# PIC_PROTO-BOARD.net
KiCad netlist of a schematic drawn in EAGLE
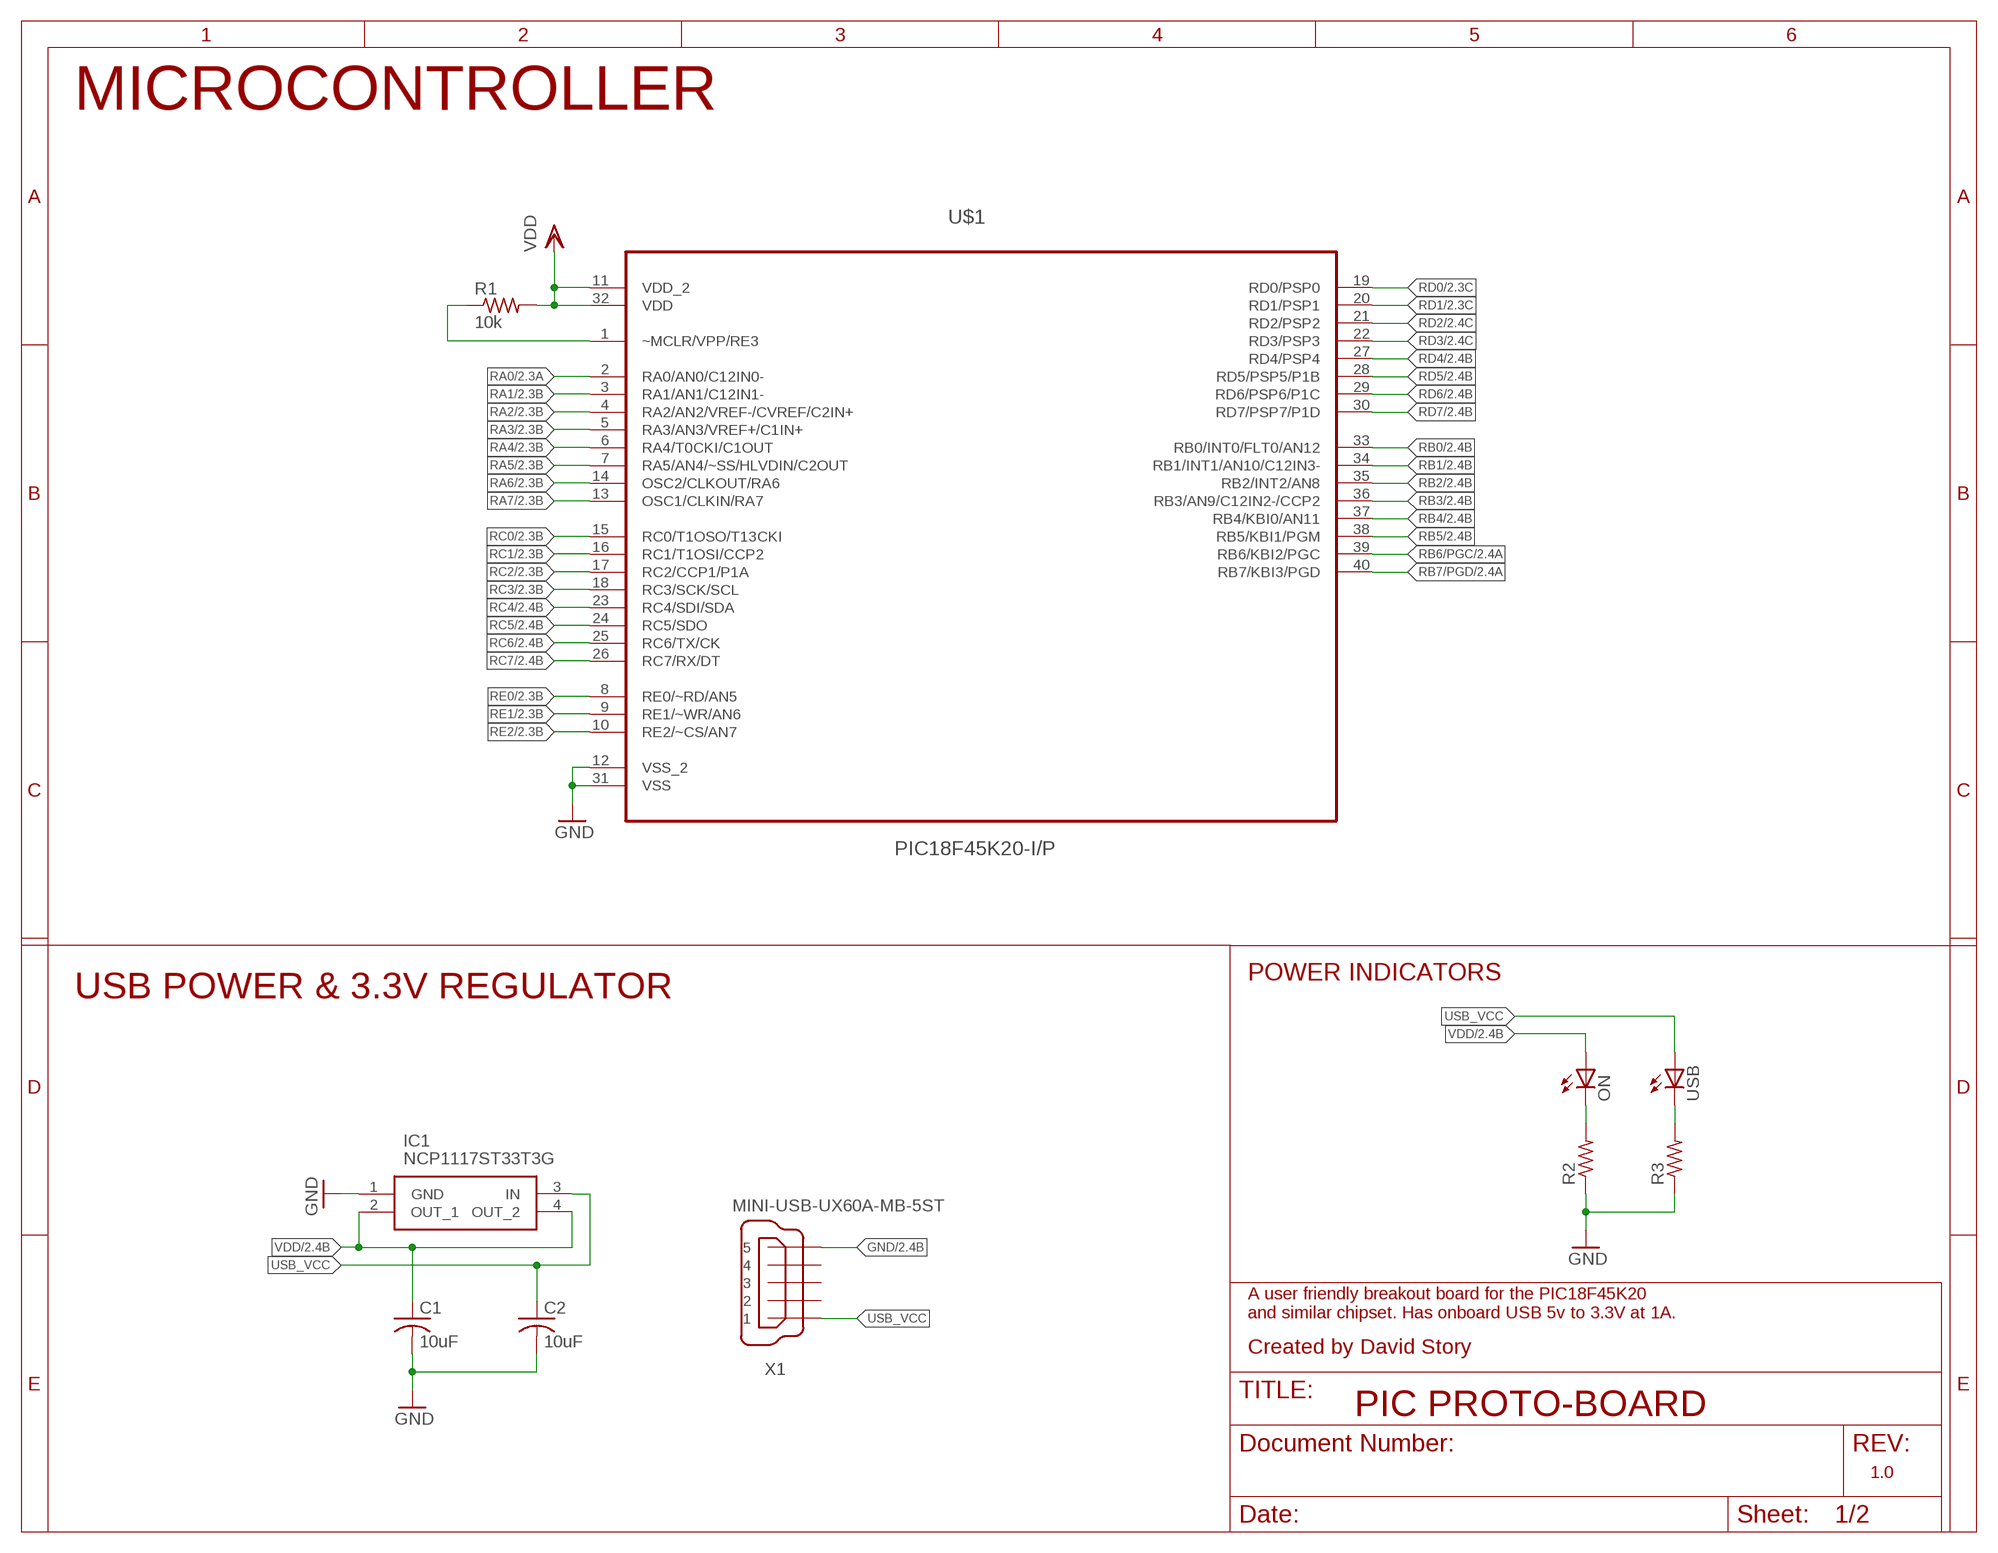
[diagram p0: schematic, sheet 1]
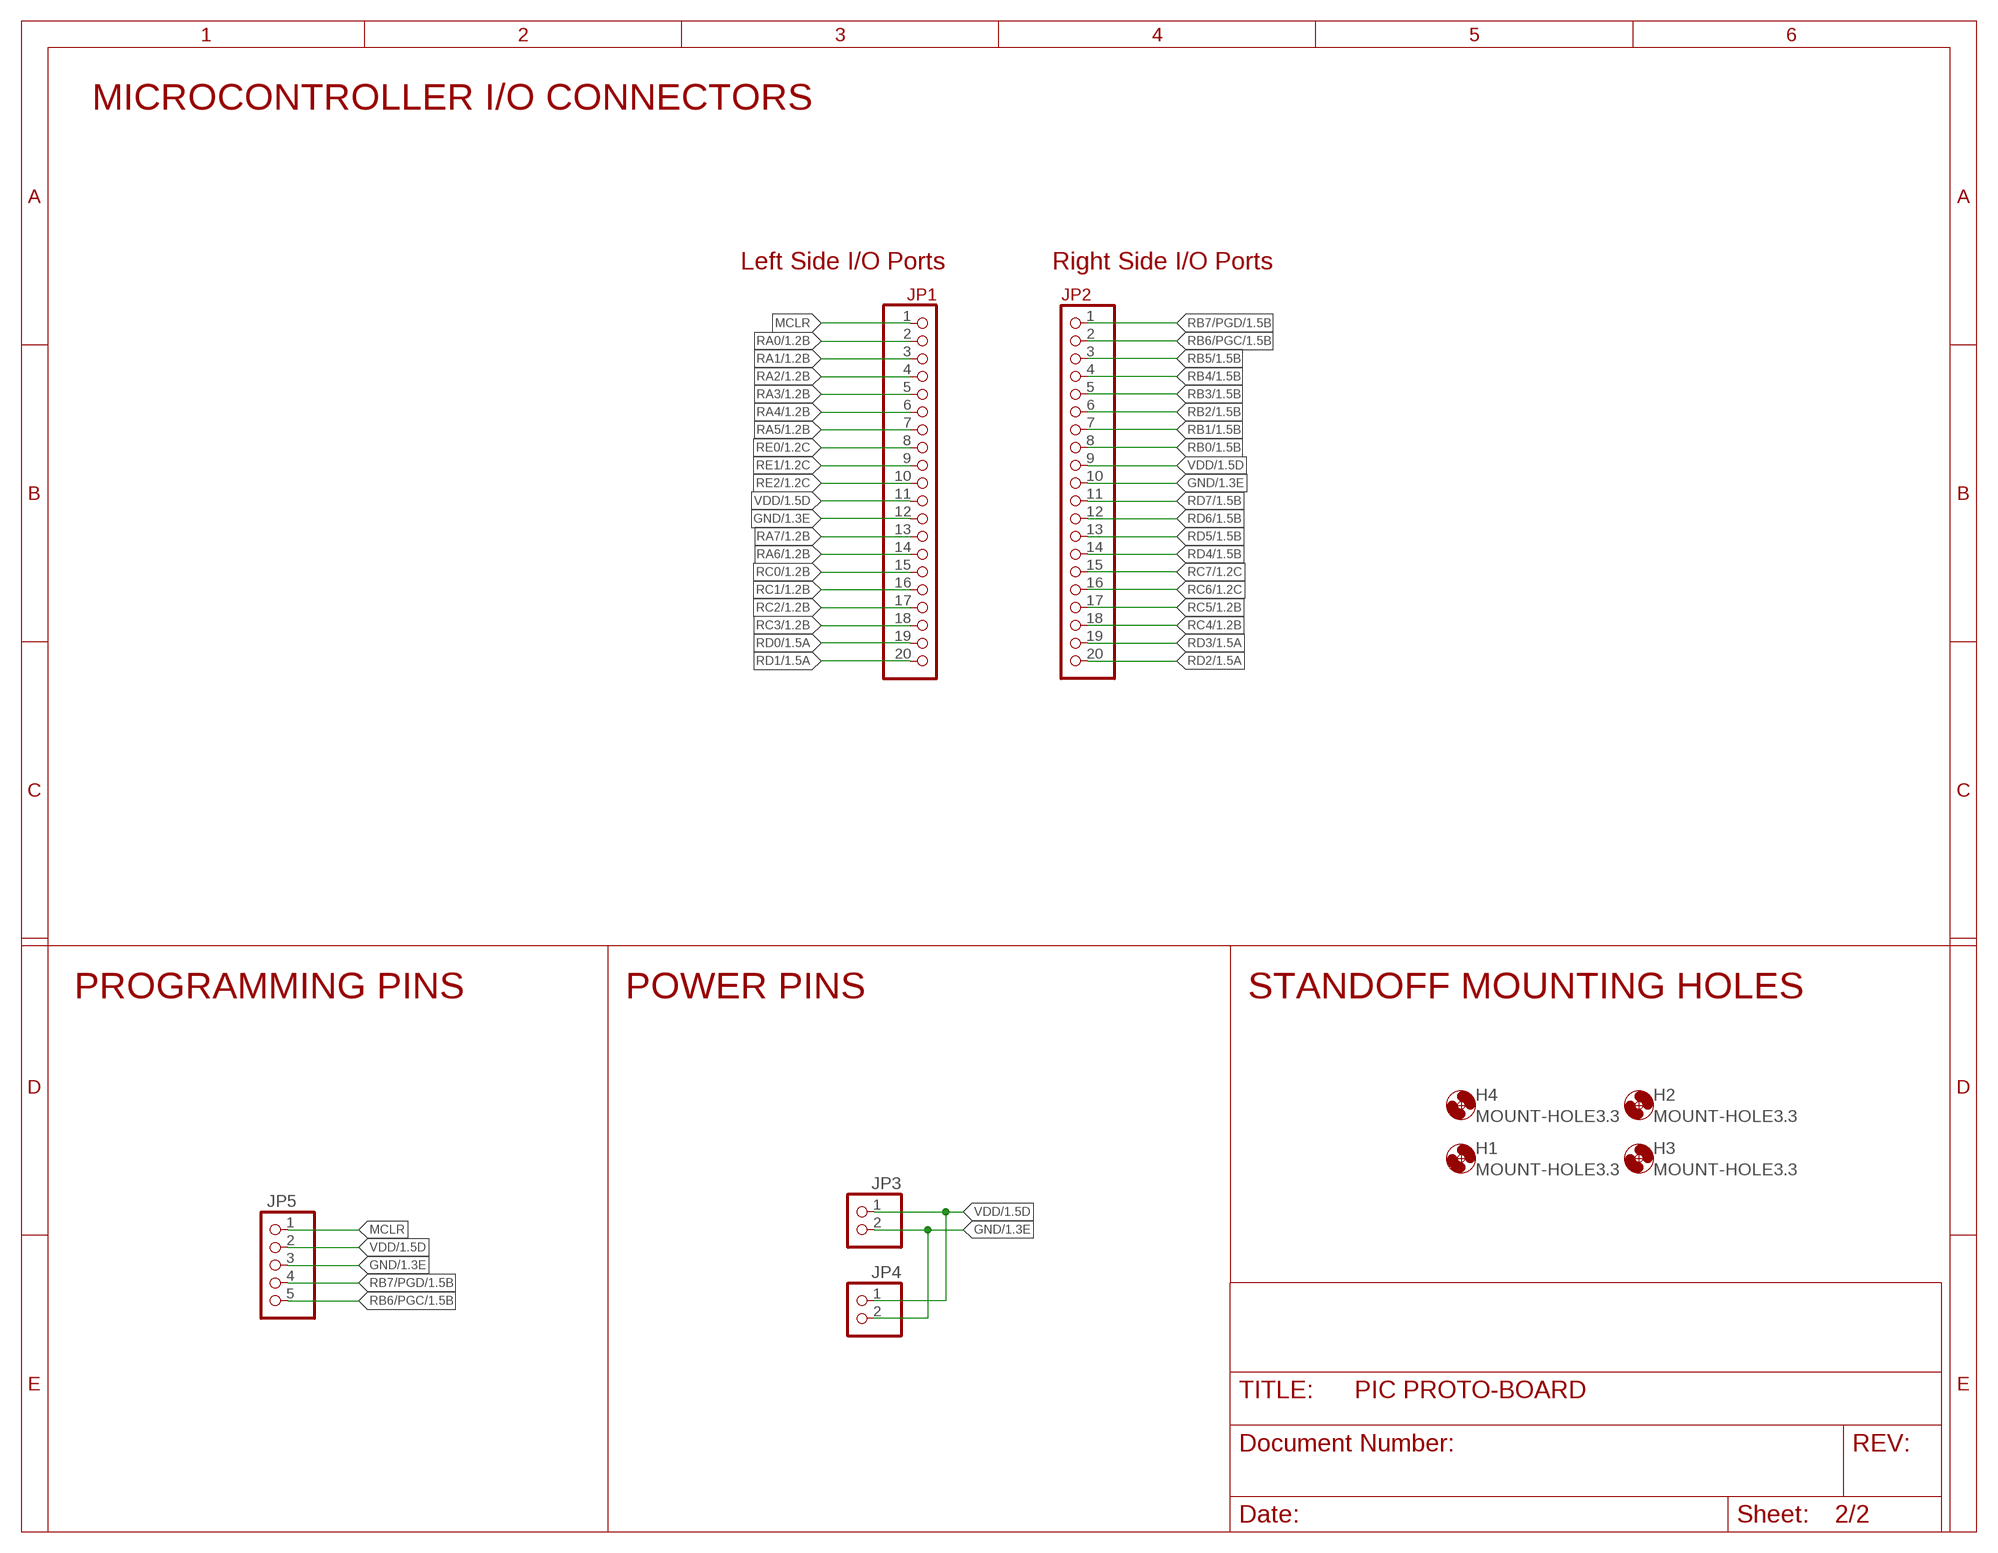
[diagram p1: schematic, sheet 2]

(export (version "E")
  (design (tool "Eeschema 10.0.6"))
  (components
    (comp (ref "C1")
      (value "10uF")
      (footprint "eagle-import:C0805")
      (libsource (lib "eagle-import") (part "C-USC0805"))
    )
    (comp (ref "C2")
      (value "10uF")
      (footprint "eagle-import:C0805")
      (libsource (lib "eagle-import") (part "C-USC0805"))
    )
    (comp (ref "IC1")
      (value "NCP1117ST33T3G")
      (footprint "eagle-import:SOT230P700X180-4N")
      (fields (field (name "MOUSER_PART_NUMBER") "863-NCP1117ST33T3G"))
      (libsource (lib "eagle-import") (part "NCP1117ST33T3G"))
    )
    (comp (ref "ON")
      (value "LEDCHIP-LED0603")
      (footprint "eagle-import:CHIP-LED0603")
      (libsource (lib "eagle-import") (part "LEDCHIP-LED0603"))
    )
    (comp (ref "R1")
      (value "10k")
      (footprint "eagle-import:R0805")
      (libsource (lib "eagle-import") (part "R-US_R0805"))
    )
    (comp (ref "R2")
      (value "R-US_R0603")
      (footprint "eagle-import:R0603")
      (libsource (lib "eagle-import") (part "R-US_R0603"))
    )
    (comp (ref "R3")
      (value "R-US_R0603")
      (footprint "eagle-import:R0603")
      (libsource (lib "eagle-import") (part "R-US_R0603"))
    )
    (comp (ref "U$1")
      (value "PIC18F45K20-I/P")
      (footprint "eagle-import:DIP254P1524X635-40")
      (libsource (lib "eagle-import") (part "PIC18F45K20-I/P"))
    )
    (comp (ref "USB")
      (value "LEDCHIP-LED0603")
      (footprint "eagle-import:CHIP-LED0603")
      (libsource (lib "eagle-import") (part "LEDCHIP-LED0603"))
    )
    (comp (ref "X1")
      (value "MINI-USB-UX60A-MB-5ST")
      (footprint "eagle-import:UX60A-MB-5ST")
      (libsource (lib "eagle-import") (part "MINI-USB-UX60A-MB-5ST"))
    )
    (comp (ref "H1")
      (value "MOUNT-HOLE3.3")
      (footprint "eagle-import:3,3")
      (libsource (lib "eagle-import") (part "MOUNT-HOLE3.3"))
    )
    (comp (ref "H2")
      (value "MOUNT-HOLE3.3")
      (footprint "eagle-import:3,3")
      (libsource (lib "eagle-import") (part "MOUNT-HOLE3.3"))
    )
    (comp (ref "H3")
      (value "MOUNT-HOLE3.3")
      (footprint "eagle-import:3,3")
      (libsource (lib "eagle-import") (part "MOUNT-HOLE3.3"))
    )
    (comp (ref "H4")
      (value "MOUNT-HOLE3.3")
      (footprint "eagle-import:3,3")
      (libsource (lib "eagle-import") (part "MOUNT-HOLE3.3"))
    )
    (comp (ref "JP1")
      (value "PINHD-1X20")
      (footprint "eagle-import:1X20")
      (libsource (lib "eagle-import") (part "PINHD-1X20"))
    )
    (comp (ref "JP2")
      (value "PINHD-1X20")
      (footprint "eagle-import:1X20")
      (libsource (lib "eagle-import") (part "PINHD-1X20"))
    )
    (comp (ref "JP3")
      (value "PINHD-1X2")
      (footprint "eagle-import:1X02")
      (libsource (lib "eagle-import") (part "PINHD-1X2"))
    )
    (comp (ref "JP4")
      (value "PINHD-1X2")
      (footprint "eagle-import:1X02")
      (libsource (lib "eagle-import") (part "PINHD-1X2"))
    )
    (comp (ref "JP5")
      (value "PINHD-1X5")
      (footprint "eagle-import:1X05")
      (libsource (lib "eagle-import") (part "PINHD-1X5"))
    )
  )
  (nets
    (net (code "1") (name "GND") (class "Default")
      (node (ref "C1") (pin "2") (pinfunction "2_2") (pintype "passive"))
      (node (ref "C2") (pin "2") (pinfunction "2_2") (pintype "passive"))
      (node (ref "IC1") (pin "1") (pinfunction "GND_1") (pintype "power_in"))
      (node (ref "JP1") (pin "12") (pinfunction "12_12") (pintype "passive"))
      (node (ref "JP2") (pin "10") (pinfunction "10_10") (pintype "passive"))
      (node (ref "JP3") (pin "2") (pinfunction "2_2") (pintype "passive"))
      (node (ref "JP4") (pin "2") (pinfunction "2_2") (pintype "passive"))
      (node (ref "JP5") (pin "3") (pinfunction "3_3") (pintype "passive"))
      (node (ref "R2") (pin "1") (pinfunction "1_1") (pintype "passive"))
      (node (ref "R3") (pin "1") (pinfunction "1_1") (pintype "passive"))
      (node (ref "U$1") (pin "12") (pinfunction "VSS_2_12") (pintype "power_in"))
      (node (ref "U$1") (pin "31") (pinfunction "VSS_31") (pintype "power_in"))
      (node (ref "X1") (pin "5") (pinfunction "5_5") (pintype "input"))
    )
    (net (code "2") (name "MCLR") (class "Default")
      (node (ref "JP1") (pin "1") (pinfunction "1_1") (pintype "passive"))
      (node (ref "JP5") (pin "1") (pinfunction "1_1") (pintype "passive"))
      (node (ref "R1") (pin "1") (pinfunction "1_1") (pintype "passive"))
      (node (ref "U$1") (pin "1") (pinfunction "~{MCLR/VPP/RE3}_1") (pintype "input"))
    )
    (net (code "3") (name "Net-(ON-PadC)") (class "Default")
      (node (ref "ON") (pin "C") (pinfunction "C_C") (pintype "passive"))
      (node (ref "R2") (pin "2") (pinfunction "2_2") (pintype "passive"))
    )
    (net (code "4") (name "Net-(R3-Pad2)") (class "Default")
      (node (ref "R3") (pin "2") (pinfunction "2_2") (pintype "passive"))
      (node (ref "USB") (pin "C") (pinfunction "C_C") (pintype "passive"))
    )
    (net (code "5") (name "RA0") (class "Default")
      (node (ref "JP1") (pin "2") (pinfunction "2_2") (pintype "passive"))
      (node (ref "U$1") (pin "2") (pinfunction "RA0/AN0/C12IN0-_2") (pintype "bidirectional"))
    )
    (net (code "6") (name "RA1") (class "Default")
      (node (ref "JP1") (pin "3") (pinfunction "3_3") (pintype "passive"))
      (node (ref "U$1") (pin "3") (pinfunction "RA1/AN1/C12IN1-_3") (pintype "bidirectional"))
    )
    (net (code "7") (name "RA2") (class "Default")
      (node (ref "JP1") (pin "4") (pinfunction "4_4") (pintype "passive"))
      (node (ref "U$1") (pin "4") (pinfunction "RA2/AN2/VREF-/CVREF/C2IN+_4") (pintype "bidirectional"))
    )
    (net (code "8") (name "RA3") (class "Default")
      (node (ref "JP1") (pin "5") (pinfunction "5_5") (pintype "passive"))
      (node (ref "U$1") (pin "5") (pinfunction "RA3/AN3/VREF+/C1IN+_5") (pintype "bidirectional"))
    )
    (net (code "9") (name "RA4") (class "Default")
      (node (ref "JP1") (pin "6") (pinfunction "6_6") (pintype "passive"))
      (node (ref "U$1") (pin "6") (pinfunction "RA4/T0CKI/C1OUT_6") (pintype "bidirectional"))
    )
    (net (code "10") (name "RA5") (class "Default")
      (node (ref "JP1") (pin "7") (pinfunction "7_7") (pintype "passive"))
      (node (ref "U$1") (pin "7") (pinfunction "RA5/AN4/~{SS/HLVDIN/C2OUT}_7") (pintype "bidirectional"))
    )
    (net (code "11") (name "RA6") (class "Default")
      (node (ref "JP1") (pin "14") (pinfunction "14_14") (pintype "passive"))
      (node (ref "U$1") (pin "14") (pinfunction "OSC2/CLKOUT/RA6_14") (pintype "bidirectional"))
    )
    (net (code "12") (name "RA7") (class "Default")
      (node (ref "JP1") (pin "13") (pinfunction "13_13") (pintype "passive"))
      (node (ref "U$1") (pin "13") (pinfunction "OSC1/CLKIN/RA7_13") (pintype "bidirectional"))
    )
    (net (code "13") (name "RB0") (class "Default")
      (node (ref "JP2") (pin "8") (pinfunction "8_8") (pintype "passive"))
      (node (ref "U$1") (pin "33") (pinfunction "RB0/INT0/FLT0/AN12_33") (pintype "bidirectional"))
    )
    (net (code "14") (name "RB1") (class "Default")
      (node (ref "JP2") (pin "7") (pinfunction "7_7") (pintype "passive"))
      (node (ref "U$1") (pin "34") (pinfunction "RB1/INT1/AN10/C12IN3-_34") (pintype "bidirectional"))
    )
    (net (code "15") (name "RB2") (class "Default")
      (node (ref "JP2") (pin "6") (pinfunction "6_6") (pintype "passive"))
      (node (ref "U$1") (pin "35") (pinfunction "RB2/INT2/AN8_35") (pintype "bidirectional"))
    )
    (net (code "16") (name "RB3") (class "Default")
      (node (ref "JP2") (pin "5") (pinfunction "5_5") (pintype "passive"))
      (node (ref "U$1") (pin "36") (pinfunction "RB3/AN9/C12IN2-/CCP2_36") (pintype "bidirectional"))
    )
    (net (code "17") (name "RB4") (class "Default")
      (node (ref "JP2") (pin "4") (pinfunction "4_4") (pintype "passive"))
      (node (ref "U$1") (pin "37") (pinfunction "RB4/KBI0/AN11_37") (pintype "bidirectional"))
    )
    (net (code "18") (name "RB5") (class "Default")
      (node (ref "JP2") (pin "3") (pinfunction "3_3") (pintype "passive"))
      (node (ref "U$1") (pin "38") (pinfunction "RB5/KBI1/PGM_38") (pintype "bidirectional"))
    )
    (net (code "19") (name "RB6{slash}PGC") (class "Default")
      (node (ref "JP2") (pin "2") (pinfunction "2_2") (pintype "passive"))
      (node (ref "JP5") (pin "5") (pinfunction "5_5") (pintype "passive"))
      (node (ref "U$1") (pin "39") (pinfunction "RB6/KBI2/PGC_39") (pintype "bidirectional"))
    )
    (net (code "20") (name "RB7{slash}PGD") (class "Default")
      (node (ref "JP2") (pin "1") (pinfunction "1_1") (pintype "passive"))
      (node (ref "JP5") (pin "4") (pinfunction "4_4") (pintype "passive"))
      (node (ref "U$1") (pin "40") (pinfunction "RB7/KBI3/PGD_40") (pintype "bidirectional"))
    )
    (net (code "21") (name "RC0") (class "Default")
      (node (ref "JP1") (pin "15") (pinfunction "15_15") (pintype "passive"))
      (node (ref "U$1") (pin "15") (pinfunction "RC0/T1OSO/T13CKI_15") (pintype "bidirectional"))
    )
    (net (code "22") (name "RC1") (class "Default")
      (node (ref "JP1") (pin "16") (pinfunction "16_16") (pintype "passive"))
      (node (ref "U$1") (pin "16") (pinfunction "RC1/T1OSI/CCP2_16") (pintype "bidirectional"))
    )
    (net (code "23") (name "RC2") (class "Default")
      (node (ref "JP1") (pin "17") (pinfunction "17_17") (pintype "passive"))
      (node (ref "U$1") (pin "17") (pinfunction "RC2/CCP1/P1A_17") (pintype "bidirectional"))
    )
    (net (code "24") (name "RC3") (class "Default")
      (node (ref "JP1") (pin "18") (pinfunction "18_18") (pintype "passive"))
      (node (ref "U$1") (pin "18") (pinfunction "RC3/SCK/SCL_18") (pintype "bidirectional"))
    )
    (net (code "25") (name "RC4") (class "Default")
      (node (ref "JP2") (pin "18") (pinfunction "18_18") (pintype "passive"))
      (node (ref "U$1") (pin "23") (pinfunction "RC4/SDI/SDA_23") (pintype "bidirectional"))
    )
    (net (code "26") (name "RC5") (class "Default")
      (node (ref "JP2") (pin "17") (pinfunction "17_17") (pintype "passive"))
      (node (ref "U$1") (pin "24") (pinfunction "RC5/SDO_24") (pintype "bidirectional"))
    )
    (net (code "27") (name "RC6") (class "Default")
      (node (ref "JP2") (pin "16") (pinfunction "16_16") (pintype "passive"))
      (node (ref "U$1") (pin "25") (pinfunction "RC6/TX/CK_25") (pintype "bidirectional"))
    )
    (net (code "28") (name "RC7") (class "Default")
      (node (ref "JP2") (pin "15") (pinfunction "15_15") (pintype "passive"))
      (node (ref "U$1") (pin "26") (pinfunction "RC7/RX/DT_26") (pintype "bidirectional"))
    )
    (net (code "29") (name "RD0") (class "Default")
      (node (ref "JP1") (pin "19") (pinfunction "19_19") (pintype "passive"))
      (node (ref "U$1") (pin "19") (pinfunction "RD0/PSP0_19") (pintype "bidirectional"))
    )
    (net (code "30") (name "RD1") (class "Default")
      (node (ref "JP1") (pin "20") (pinfunction "20_20") (pintype "passive"))
      (node (ref "U$1") (pin "20") (pinfunction "RD1/PSP1_20") (pintype "bidirectional"))
    )
    (net (code "31") (name "RD2") (class "Default")
      (node (ref "JP2") (pin "20") (pinfunction "20_20") (pintype "passive"))
      (node (ref "U$1") (pin "21") (pinfunction "RD2/PSP2_21") (pintype "bidirectional"))
    )
    (net (code "32") (name "RD3") (class "Default")
      (node (ref "JP2") (pin "19") (pinfunction "19_19") (pintype "passive"))
      (node (ref "U$1") (pin "22") (pinfunction "RD3/PSP3_22") (pintype "bidirectional"))
    )
    (net (code "33") (name "RD4") (class "Default")
      (node (ref "JP2") (pin "14") (pinfunction "14_14") (pintype "passive"))
      (node (ref "U$1") (pin "27") (pinfunction "RD4/PSP4_27") (pintype "bidirectional"))
    )
    (net (code "34") (name "RD5") (class "Default")
      (node (ref "JP2") (pin "13") (pinfunction "13_13") (pintype "passive"))
      (node (ref "U$1") (pin "28") (pinfunction "RD5/PSP5/P1B_28") (pintype "bidirectional"))
    )
    (net (code "35") (name "RD6") (class "Default")
      (node (ref "JP2") (pin "12") (pinfunction "12_12") (pintype "passive"))
      (node (ref "U$1") (pin "29") (pinfunction "RD6/PSP6/P1C_29") (pintype "bidirectional"))
    )
    (net (code "36") (name "RD7") (class "Default")
      (node (ref "JP2") (pin "11") (pinfunction "11_11") (pintype "passive"))
      (node (ref "U$1") (pin "30") (pinfunction "RD7/PSP7/P1D_30") (pintype "bidirectional"))
    )
    (net (code "37") (name "RE0") (class "Default")
      (node (ref "JP1") (pin "8") (pinfunction "8_8") (pintype "passive"))
      (node (ref "U$1") (pin "8") (pinfunction "RE0/~{RD/AN5}_8") (pintype "bidirectional"))
    )
    (net (code "38") (name "RE1") (class "Default")
      (node (ref "JP1") (pin "9") (pinfunction "9_9") (pintype "passive"))
      (node (ref "U$1") (pin "9") (pinfunction "RE1/~{WR/AN6}_9") (pintype "bidirectional"))
    )
    (net (code "39") (name "RE2") (class "Default")
      (node (ref "JP1") (pin "10") (pinfunction "10_10") (pintype "passive"))
      (node (ref "U$1") (pin "10") (pinfunction "RE2/~{CS/AN7}_10") (pintype "bidirectional"))
    )
    (net (code "40") (name "USB_VCC") (class "Default")
      (node (ref "C2") (pin "1") (pinfunction "1_1") (pintype "passive"))
      (node (ref "IC1") (pin "3") (pinfunction "IN_3") (pintype "input"))
      (node (ref "USB") (pin "A") (pinfunction "A_A") (pintype "passive"))
      (node (ref "X1") (pin "1") (pinfunction "1_1") (pintype "input"))
    )
    (net (code "41") (name "VDD") (class "Default")
      (node (ref "C1") (pin "1") (pinfunction "1_1") (pintype "passive"))
      (node (ref "IC1") (pin "2") (pinfunction "OUT_1_2") (pintype "output"))
      (node (ref "IC1") (pin "4") (pinfunction "OUT_2_4") (pintype "output"))
      (node (ref "JP1") (pin "11") (pinfunction "11_11") (pintype "passive"))
      (node (ref "JP2") (pin "9") (pinfunction "9_9") (pintype "passive"))
      (node (ref "JP3") (pin "1") (pinfunction "1_1") (pintype "passive"))
      (node (ref "JP4") (pin "1") (pinfunction "1_1") (pintype "passive"))
      (node (ref "JP5") (pin "2") (pinfunction "2_2") (pintype "passive"))
      (node (ref "ON") (pin "A") (pinfunction "A_A") (pintype "passive"))
      (node (ref "R1") (pin "2") (pinfunction "2_2") (pintype "passive"))
      (node (ref "U$1") (pin "11") (pinfunction "VDD_2_11") (pintype "power_in"))
      (node (ref "U$1") (pin "32") (pinfunction "VDD_32") (pintype "power_in"))
    )
    (net (code "42") (name "unconnected-(X1-Pad2)") (class "Default")
      (node (ref "X1") (pin "2") (pinfunction "2_2") (pintype "input"))
    )
    (net (code "43") (name "unconnected-(X1-Pad3)") (class "Default")
      (node (ref "X1") (pin "3") (pinfunction "3_3") (pintype "input"))
    )
    (net (code "44") (name "unconnected-(X1-Pad4)") (class "Default")
      (node (ref "X1") (pin "4") (pinfunction "4_4") (pintype "input"))
    )
  )
)
